# 1-MCU.net
KiCad netlist of a schematic drawn in Altium Designer
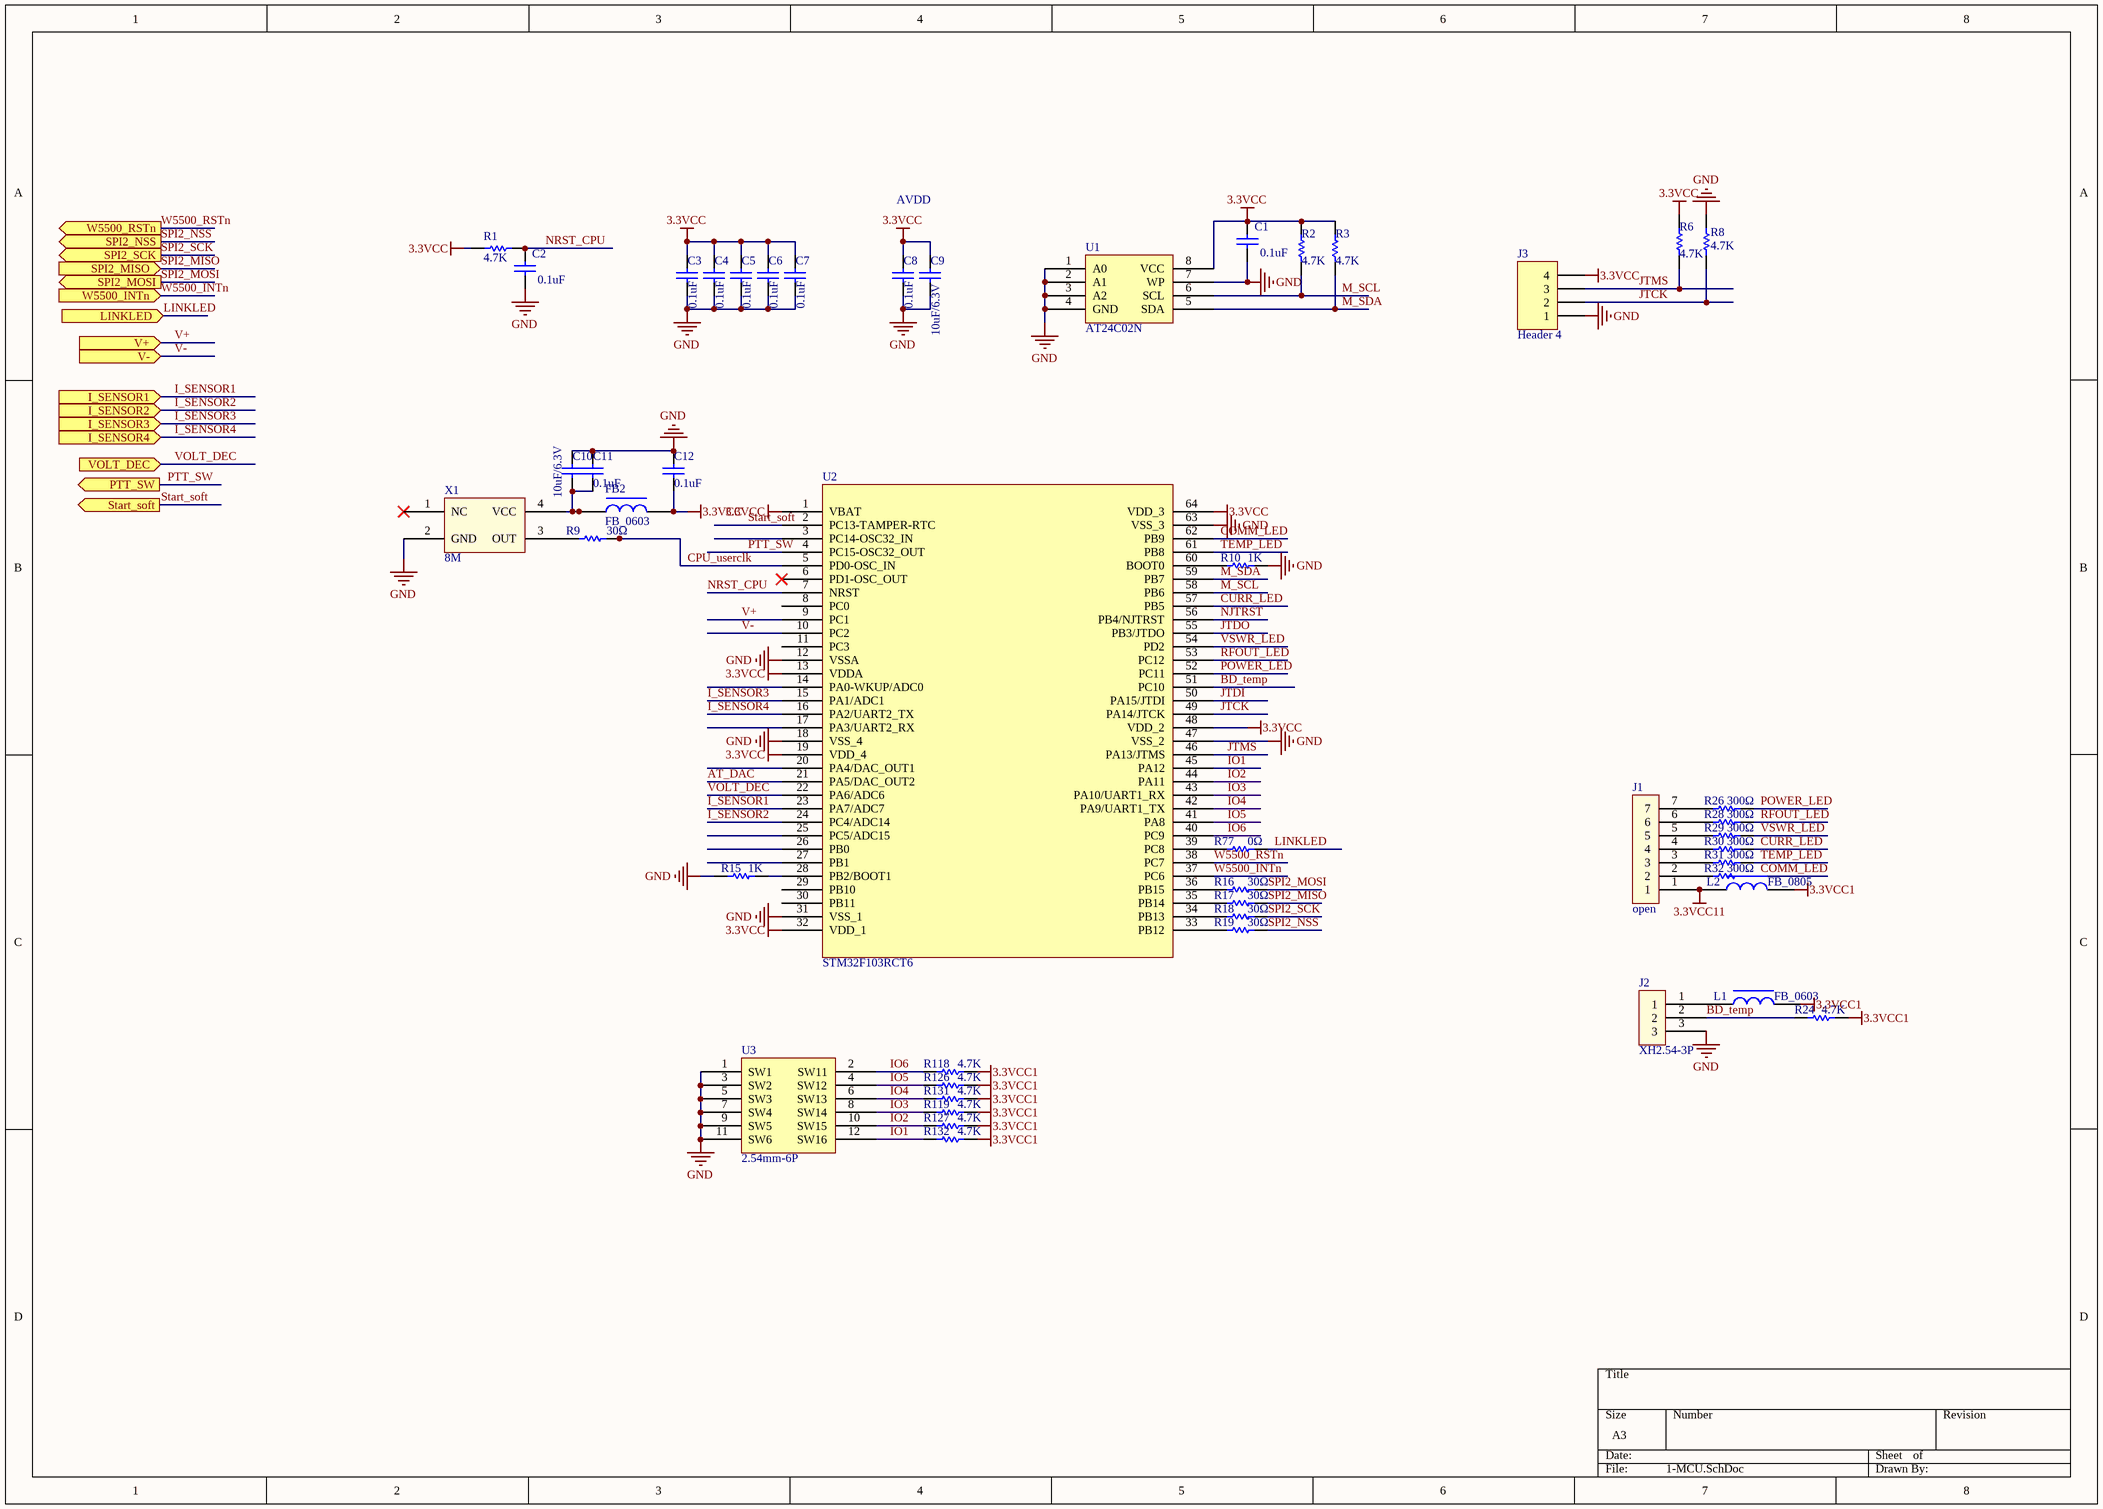
[diagram p0: 1-MCU.SchDoc]

(export (version "E")
  (design (tool "Eeschema 10.0.6"))
  (components
    (comp (ref "C1")
      (value "0.1uF")
      (footprint "C0603")
      (description "贴片电容_GRM188R71H104KA01D_0.1uF±10%,50V,0603")
      (libsource (lib "20贴片电容0603") (part "0.1uF贴片电容"))
    )
    (comp (ref "C2")
      (value "0.1uF")
      (footprint "C0603")
      (description "贴片电容_GRM188R71H104KA01D_0.1uF±10%,50V,0603")
      (libsource (lib "20贴片电容0603") (part "0.1uF贴片电容"))
    )
    (comp (ref "C3")
      (value "0.1uF")
      (footprint "C0603")
      (description "贴片电容_GRM188R71H104KA01D_0.1uF±10%,50V,0603")
      (libsource (lib "20贴片电容0603") (part "0.1uF贴片电容"))
    )
    (comp (ref "C4")
      (value "0.1uF")
      (footprint "C0603")
      (description "贴片电容_GRM188R71H104KA01D_0.1uF±10%,50V,0603")
      (libsource (lib "20贴片电容0603") (part "0.1uF贴片电容"))
    )
    (comp (ref "C5")
      (value "0.1uF")
      (footprint "C0603")
      (description "贴片电容_GRM188R71H104KA01D_0.1uF±10%,50V,0603")
      (libsource (lib "20贴片电容0603") (part "0.1uF贴片电容"))
    )
    (comp (ref "C6")
      (value "0.1uF")
      (footprint "C0603")
      (description "贴片电容_GRM188R71H104KA01D_0.1uF±10%,50V,0603")
      (libsource (lib "20贴片电容0603") (part "0.1uF贴片电容"))
    )
    (comp (ref "C7")
      (value "0.1uF")
      (footprint "C0603")
      (description "贴片电容_GRM188R71H104KA01D_0.1uF±10%,50V,0603")
      (libsource (lib "20贴片电容0603") (part "0.1uF贴片电容"))
    )
    (comp (ref "C8")
      (value "0.1uF")
      (footprint "C0603")
      (description "贴片电容_GRM188R71H104KA01D_0.1uF±10%,50V,0603")
      (libsource (lib "20贴片电容0603") (part "0.1uF贴片电容"))
    )
    (comp (ref "C9")
      (value "10uF/6.3V")
      (footprint "C0603")
      (description "贴片电容_GRM188R60J106ME47D_10uF±20%,6.3V,0603")
      (libsource (lib "20贴片电容0603") (part "10uF贴片电容"))
    )
    (comp (ref "C10")
      (value "10uF/6.3V")
      (footprint "C0603")
      (description "贴片电容_GRM188R60J106ME47D_10uF±20%,6.3V,0603")
      (libsource (lib "20贴片电容0603") (part "10uF贴片电容"))
    )
    (comp (ref "C11")
      (value "0.1uF")
      (footprint "C0603")
      (description "贴片电容_GRM188R71H104KA01D_0.1uF±10%,50V,0603")
      (libsource (lib "20贴片电容0603") (part "0.1uF贴片电容"))
    )
    (comp (ref "C12")
      (value "0.1uF")
      (footprint "C0603")
      (description "贴片电容_GRM188R71H104KA01D_0.1uF±10%,50V,0603")
      (libsource (lib "20贴片电容0603") (part "0.1uF贴片电容"))
    )
    (comp (ref "FB2")
      (value "FB_0603")
      (footprint "L0603")
      (description "贴片磁珠_100R,0603")
      (libsource (lib "32贴片磁珠0603") (part "0603贴片磁珠"))
    )
    (comp (ref "J1")
      (value "open")
      (footprint "KF2510-7P -2R54-17R8x6R0-wanzhen")
      (description "连接器_KF2510-7P_直插,间距2.54mm")
      (libsource (lib "91连接器") (part "KF2510-7P连接器"))
    )
    (comp (ref "J2")
      (value "XH2.54-3P")
      (footprint "pcblib:XH2.54mm-10R0x7R0--zhizhen")
      (description "连接器_XH2.54-3P_弯针,间距2.54mm")
      (libsource (lib "91连接器") (part "XH2.54-3P"))
    )
    (comp (ref "J3")
      (value "Header 4")
      (footprint "HDR1X4")
      (description "Header, 4-Pin")
      (fields (field (name "PUBLISHER") "Altium Limited"))
      (libsource (lib "Miscellaneous Connectors") (part "Header 4"))
    )
    (comp (ref "L1")
      (value "FB_0603")
      (footprint "L0603")
      (description "贴片磁珠_600R,0805")
      (libsource (lib "33贴片磁珠0805") (part "0805贴片磁珠"))
    )
    (comp (ref "L2")
      (value "FB_0805")
      (footprint "L0805")
      (description "贴片磁珠_600R,0805")
      (libsource (lib "33贴片磁珠0805") (part "0805贴片磁珠"))
    )
    (comp (ref "R1")
      (value "4.7K")
      (footprint "R0603")
      (description "贴片电阻_4.7K±5%,0603")
      (libsource (lib "10贴片电阻0603") (part "4.7K贴片电阻"))
    )
    (comp (ref "R2")
      (value "4.7K")
      (footprint "R0603")
      (description "贴片电阻_4.7K±5%,0603")
      (libsource (lib "10贴片电阻0603") (part "4.7K贴片电阻"))
    )
    (comp (ref "R3")
      (value "4.7K")
      (footprint "R0603")
      (description "贴片电阻_4.7K±5%,0603")
      (libsource (lib "10贴片电阻0603") (part "4.7K贴片电阻"))
    )
    (comp (ref "R6")
      (value "4.7K")
      (footprint "R0603")
      (description "贴片电阻_4.7K±5%,0603")
      (libsource (lib "10贴片电阻0603") (part "4.7K贴片电阻"))
    )
    (comp (ref "R8")
      (value "4.7K")
      (footprint "R0603")
      (description "贴片电阻_1K±5%,0603")
      (libsource (lib "10贴片电阻0603") (part "1K贴片电阻"))
    )
    (comp (ref "R9")
      (value "30Ω")
      (footprint "R0603")
      (description "贴片电阻_30Ω±5%,0603")
      (libsource (lib "10贴片电阻0603") (part "30Ω贴片电阻"))
    )
    (comp (ref "R10")
      (value "1K")
      (footprint "R0603")
      (description "贴片电阻_1K±5%,0603")
      (libsource (lib "10贴片电阻0603") (part "1K贴片电阻"))
    )
    (comp (ref "R15")
      (value "1K")
      (footprint "R0603")
      (description "贴片电阻_1K±5%,0603")
      (libsource (lib "10贴片电阻0603") (part "1K贴片电阻"))
    )
    (comp (ref "R16")
      (value "30Ω")
      (footprint "R0603")
      (description "贴片电阻_30Ω±5%,0603")
      (libsource (lib "10贴片电阻0603") (part "30Ω贴片电阻"))
    )
    (comp (ref "R17")
      (value "30Ω")
      (footprint "R0603")
      (description "贴片电阻_30Ω±5%,0603")
      (libsource (lib "10贴片电阻0603") (part "30Ω贴片电阻"))
    )
    (comp (ref "R18")
      (value "30Ω")
      (footprint "R0603")
      (description "贴片电阻_30Ω±5%,0603")
      (libsource (lib "10贴片电阻0603") (part "30Ω贴片电阻"))
    )
    (comp (ref "R19")
      (value "30Ω")
      (footprint "R0603")
      (description "贴片电阻_30Ω±5%,0603")
      (libsource (lib "10贴片电阻0603") (part "30Ω贴片电阻"))
    )
    (comp (ref "R24")
      (value "4.7K")
      (footprint "R0603")
      (description "贴片电阻_4.7K±5%,0603")
      (libsource (lib "10贴片电阻0603") (part "4.7K贴片电阻"))
    )
    (comp (ref "R26")
      (value "300Ω")
      (footprint "R0603")
      (description "贴片电阻_300Ω±5%,0603")
      (libsource (lib "10贴片电阻0603") (part "300Ω贴片电阻"))
    )
    (comp (ref "R28")
      (value "300Ω")
      (footprint "R0603")
      (description "贴片电阻_300Ω±5%,0603")
      (libsource (lib "10贴片电阻0603") (part "300Ω贴片电阻"))
    )
    (comp (ref "R29")
      (value "300Ω")
      (footprint "R0603")
      (description "贴片电阻_300Ω±5%,0603")
      (libsource (lib "10贴片电阻0603") (part "300Ω贴片电阻"))
    )
    (comp (ref "R30")
      (value "300Ω")
      (footprint "R0603")
      (description "贴片电阻_300Ω±5%,0603")
      (libsource (lib "10贴片电阻0603") (part "300Ω贴片电阻"))
    )
    (comp (ref "R31")
      (value "300Ω")
      (footprint "R0603")
      (description "贴片电阻_300Ω±5%,0603")
      (libsource (lib "10贴片电阻0603") (part "300Ω贴片电阻"))
    )
    (comp (ref "R32")
      (value "300Ω")
      (footprint "R0603")
      (description "贴片电阻_300Ω±5%,0603")
      (libsource (lib "10贴片电阻0603") (part "300Ω贴片电阻"))
    )
    (comp (ref "R77")
      (value "0Ω")
      (footprint "R0603")
      (description "贴片电阻_0Ω±5%,0603")
      (libsource (lib "10贴片电阻0603") (part "0Ω贴片电阻"))
    )
    (comp (ref "R118")
      (value "4.7K")
      (footprint "R0603")
      (description "贴片电阻_4.7K±5%,0603")
      (libsource (lib "10贴片电阻0603") (part "1.5K贴片电阻"))
    )
    (comp (ref "R119")
      (value "4.7K")
      (footprint "R0603")
      (description "贴片电阻_4.7K±5%,0603")
      (libsource (lib "10贴片电阻0603") (part "1.5K贴片电阻"))
    )
    (comp (ref "R126")
      (value "4.7K")
      (footprint "R0603")
      (description "贴片电阻_4.7K±5%,0603")
      (libsource (lib "10贴片电阻0603") (part "1.5K贴片电阻"))
    )
    (comp (ref "R127")
      (value "4.7K")
      (footprint "R0603")
      (description "贴片电阻_4.7K±5%,0603")
      (libsource (lib "10贴片电阻0603") (part "1.5K贴片电阻"))
    )
    (comp (ref "R131")
      (value "4.7K")
      (footprint "R0603")
      (description "贴片电阻_4.7K±5%,0603")
      (libsource (lib "10贴片电阻0603") (part "1.5K贴片电阻"))
    )
    (comp (ref "R132")
      (value "4.7K")
      (footprint "R0603")
      (description "贴片电阻_4.7K±5%,0603")
      (libsource (lib "10贴片电阻0603") (part "1.5K贴片电阻"))
    )
    (comp (ref "U1")
      (value "AT24C02N")
      (footprint "SOIC8_1R27_3R9x4R9")
      (description "EEPROM_AT24C02N_SOIC8")
      (libsource (lib "82存储器") (part "AT24C02N"))
    )
    (comp (ref "U2")
      (value "STM32F103RCT6")
      (footprint "LQFP64-0R50-10x10")
      (description "MCU_STM32F103RCT6_32bit,LQFP64")
      (libsource (lib "71单片机") (part "STM32F103RCT6"))
    )
    (comp (ref "U3")
      (value "2.54mm-6P")
      (footprint "pcblib:con12TM-2R54-2X6-boma")
      (description "拨码开关_2.54mm-6P_侧拨")
      (libsource (lib "81开关&门电路芯片") (part "拨码开关"))
    )
    (comp (ref "X1")
      (value "8M")
      (footprint "CRY4SM-5R0x7R0")
      (description "贴片有源晶振_8M,20ppm,封装5x7")
      (libsource (lib "60振荡器") (part "16M贴片有源晶振"))
    )
  )
  (nets
    (net (code "1") (name "/AT_DAC") (class "Default")
      (node (ref "U2") (pin "21") (pinfunction "PA5/DAC_OUT2_21") (pintype "passive"))
    )
    (net (code "2") (name "/BD_temp") (class "Default")
      (node (ref "J2") (pin "2") (pinfunction "2_2") (pintype "passive"))
      (node (ref "R24") (pin "2") (pinfunction "2_2") (pintype "passive"))
      (node (ref "U2") (pin "51") (pinfunction "PC10_51") (pintype "passive"))
    )
    (net (code "3") (name "/COMM_LED") (class "Default")
      (node (ref "R32") (pin "2") (pinfunction "2_2") (pintype "passive"))
      (node (ref "U2") (pin "62") (pinfunction "PB9_62") (pintype "passive"))
    )
    (net (code "4") (name "/CPU_userclk") (class "Default")
      (node (ref "R9") (pin "2") (pinfunction "2_2") (pintype "passive"))
      (node (ref "U2") (pin "5") (pinfunction "PD0-OSC_IN_5") (pintype "passive"))
    )
    (net (code "5") (name "/CURR_LED") (class "Default")
      (node (ref "R30") (pin "2") (pinfunction "2_2") (pintype "passive"))
      (node (ref "U2") (pin "57") (pinfunction "PB5_57") (pintype "passive"))
    )
    (net (code "6") (name "/IO1") (class "Default")
      (node (ref "R132") (pin "1") (pinfunction "1_1") (pintype "passive"))
      (node (ref "U2") (pin "45") (pinfunction "PA12_45") (pintype "passive"))
      (node (ref "U3") (pin "12") (pinfunction "SW16_12") (pintype "passive"))
    )
    (net (code "7") (name "/IO2") (class "Default")
      (node (ref "R127") (pin "1") (pinfunction "1_1") (pintype "passive"))
      (node (ref "U2") (pin "44") (pinfunction "PA11_44") (pintype "passive"))
      (node (ref "U3") (pin "10") (pinfunction "SW15_10") (pintype "passive"))
    )
    (net (code "8") (name "/IO3") (class "Default")
      (node (ref "R119") (pin "1") (pinfunction "1_1") (pintype "passive"))
      (node (ref "U2") (pin "43") (pinfunction "PA10/UART1_RX_43") (pintype "passive"))
      (node (ref "U3") (pin "8") (pinfunction "SW14_8") (pintype "passive"))
    )
    (net (code "9") (name "/IO4") (class "Default")
      (node (ref "R131") (pin "1") (pinfunction "1_1") (pintype "passive"))
      (node (ref "U2") (pin "42") (pinfunction "PA9/UART1_TX_42") (pintype "passive"))
      (node (ref "U3") (pin "6") (pinfunction "SW13_6") (pintype "passive"))
    )
    (net (code "10") (name "/IO5") (class "Default")
      (node (ref "R126") (pin "1") (pinfunction "1_1") (pintype "passive"))
      (node (ref "U2") (pin "41") (pinfunction "PA8_41") (pintype "passive"))
      (node (ref "U3") (pin "4") (pinfunction "SW12_4") (pintype "passive"))
    )
    (net (code "11") (name "/IO6") (class "Default")
      (node (ref "R118") (pin "1") (pinfunction "1_1") (pintype "passive"))
      (node (ref "U2") (pin "40") (pinfunction "PC9_40") (pintype "passive"))
      (node (ref "U3") (pin "2") (pinfunction "SW11_2") (pintype "passive"))
    )
    (net (code "12") (name "/I_SENSOR1") (class "Default")
      (node (ref "U2") (pin "23") (pinfunction "PA7/ADC7_23") (pintype "passive"))
    )
    (net (code "13") (name "/I_SENSOR2") (class "Default")
      (node (ref "U2") (pin "24") (pinfunction "PC4/ADC14_24") (pintype "passive"))
    )
    (net (code "14") (name "/I_SENSOR3") (class "Default")
      (node (ref "U2") (pin "15") (pinfunction "PA1/ADC1_15") (pintype "passive"))
    )
    (net (code "15") (name "/I_SENSOR4") (class "Default")
      (node (ref "U2") (pin "16") (pinfunction "PA2/UART2_TX_16") (pintype "passive"))
    )
    (net (code "16") (name "/JTCK") (class "Default")
      (node (ref "J3") (pin "2") (pinfunction "2_2") (pintype "passive"))
      (node (ref "R8") (pin "2") (pinfunction "2_2") (pintype "passive"))
      (node (ref "U2") (pin "49") (pinfunction "PA14/JTCK_49") (pintype "passive"))
    )
    (net (code "17") (name "/JTDI") (class "Default")
      (node (ref "U2") (pin "50") (pinfunction "PA15/JTDI_50") (pintype "passive"))
    )
    (net (code "18") (name "/JTDO") (class "Default")
      (node (ref "U2") (pin "55") (pinfunction "PB3/JTDO_55") (pintype "passive"))
    )
    (net (code "19") (name "/JTMS") (class "Default")
      (node (ref "J3") (pin "3") (pinfunction "3_3") (pintype "passive"))
      (node (ref "R6") (pin "1") (pinfunction "1_1") (pintype "passive"))
      (node (ref "U2") (pin "46") (pinfunction "PA13/JTMS_46") (pintype "passive"))
    )
    (net (code "20") (name "/LINKLED") (class "Default")
      (node (ref "R77") (pin "2") (pinfunction "2_2") (pintype "passive"))
    )
    (net (code "21") (name "/M_SCL") (class "Default")
      (node (ref "R2") (pin "1") (pinfunction "1_1") (pintype "passive"))
      (node (ref "U1") (pin "6") (pinfunction "SCL_6") (pintype "passive"))
      (node (ref "U2") (pin "58") (pinfunction "PB6_58") (pintype "passive"))
    )
    (net (code "22") (name "/M_SDA") (class "Default")
      (node (ref "R3") (pin "1") (pinfunction "1_1") (pintype "passive"))
      (node (ref "U1") (pin "5") (pinfunction "SDA_5") (pintype "passive"))
      (node (ref "U2") (pin "59") (pinfunction "PB7_59") (pintype "passive"))
    )
    (net (code "23") (name "/NJTRST") (class "Default")
      (node (ref "U2") (pin "56") (pinfunction "PB4/NJTRST_56") (pintype "passive"))
    )
    (net (code "24") (name "/NRST_CPU") (class "Default")
      (node (ref "C2") (pin "2") (pinfunction "2_2") (pintype "passive"))
      (node (ref "R1") (pin "1") (pinfunction "1_1") (pintype "passive"))
      (node (ref "U2") (pin "7") (pinfunction "NRST_7") (pintype "passive"))
    )
    (net (code "25") (name "/POWER_LED") (class "Default")
      (node (ref "R26") (pin "2") (pinfunction "2_2") (pintype "passive"))
      (node (ref "U2") (pin "52") (pinfunction "PC11_52") (pintype "passive"))
    )
    (net (code "26") (name "/PTT_SW") (class "Default")
      (node (ref "U2") (pin "4") (pinfunction "PC15-OSC32_OUT_4") (pintype "passive"))
    )
    (net (code "27") (name "/RFOUT_LED") (class "Default")
      (node (ref "R28") (pin "2") (pinfunction "2_2") (pintype "passive"))
      (node (ref "U2") (pin "53") (pinfunction "PC12_53") (pintype "passive"))
    )
    (net (code "28") (name "/SPI2_MISO") (class "Default")
      (node (ref "R17") (pin "2") (pinfunction "2_2") (pintype "passive"))
    )
    (net (code "29") (name "/SPI2_MOSI") (class "Default")
      (node (ref "R16") (pin "2") (pinfunction "2_2") (pintype "passive"))
    )
    (net (code "30") (name "/SPI2_NSS") (class "Default")
      (node (ref "R19") (pin "2") (pinfunction "2_2") (pintype "passive"))
    )
    (net (code "31") (name "/SPI2_SCK") (class "Default")
      (node (ref "R18") (pin "2") (pinfunction "2_2") (pintype "passive"))
    )
    (net (code "32") (name "/Start_soft") (class "Default")
      (node (ref "U2") (pin "2") (pinfunction "PC13-TAMPER-RTC_2") (pintype "passive"))
    )
    (net (code "33") (name "/TEMP_LED") (class "Default")
      (node (ref "R31") (pin "2") (pinfunction "2_2") (pintype "passive"))
      (node (ref "U2") (pin "61") (pinfunction "PB8_61") (pintype "passive"))
    )
    (net (code "34") (name "/V+") (class "Default")
      (node (ref "U2") (pin "9") (pinfunction "PC1_9") (pintype "passive"))
    )
    (net (code "35") (name "/V-") (class "Default")
      (node (ref "U2") (pin "10") (pinfunction "PC2_10") (pintype "passive"))
    )
    (net (code "36") (name "/VOLT_DEC") (class "Default")
      (node (ref "U2") (pin "22") (pinfunction "PA6/ADC6_22") (pintype "passive"))
    )
    (net (code "37") (name "/VSWR_LED") (class "Default")
      (node (ref "R29") (pin "2") (pinfunction "2_2") (pintype "passive"))
      (node (ref "U2") (pin "54") (pinfunction "PD2_54") (pintype "passive"))
    )
    (net (code "38") (name "/W5500_INTn") (class "Default")
      (node (ref "U2") (pin "37") (pinfunction "PC6_37") (pintype "passive"))
    )
    (net (code "39") (name "/W5500_RSTn") (class "Default")
      (node (ref "U2") (pin "38") (pinfunction "PC7_38") (pintype "passive"))
    )
    (net (code "40") (name "3.3VCC") (class "Default")
      (node (ref "C1") (pin "2") (pinfunction "2_2") (pintype "passive"))
      (node (ref "C12") (pin "1") (pinfunction "1_1") (pintype "passive"))
      (node (ref "C3") (pin "2") (pinfunction "2_2") (pintype "passive"))
      (node (ref "C4") (pin "2") (pinfunction "2_2") (pintype "passive"))
      (node (ref "C5") (pin "2") (pinfunction "2_2") (pintype "passive"))
      (node (ref "C6") (pin "2") (pinfunction "2_2") (pintype "passive"))
      (node (ref "C7") (pin "2") (pinfunction "2_2") (pintype "passive"))
      (node (ref "C8") (pin "2") (pinfunction "2_2") (pintype "passive"))
      (node (ref "C9") (pin "2") (pinfunction "2_2") (pintype "passive"))
      (node (ref "FB2") (pin "2") (pinfunction "2_2") (pintype "passive"))
      (node (ref "J3") (pin "4") (pinfunction "4_4") (pintype "passive"))
      (node (ref "R1") (pin "2") (pinfunction "2_2") (pintype "passive"))
      (node (ref "R2") (pin "2") (pinfunction "2_2") (pintype "passive"))
      (node (ref "R3") (pin "2") (pinfunction "2_2") (pintype "passive"))
      (node (ref "R6") (pin "2") (pinfunction "2_2") (pintype "passive"))
      (node (ref "U1") (pin "8") (pinfunction "VCC_8") (pintype "passive"))
      (node (ref "U2") (pin "1") (pinfunction "VBAT_1") (pintype "passive"))
      (node (ref "U2") (pin "13") (pinfunction "VDDA_13") (pintype "passive"))
      (node (ref "U2") (pin "19") (pinfunction "VDD_4_19") (pintype "passive"))
      (node (ref "U2") (pin "32") (pinfunction "VDD_1_32") (pintype "passive"))
      (node (ref "U2") (pin "48") (pinfunction "VDD_2_48") (pintype "passive"))
      (node (ref "U2") (pin "64") (pinfunction "VDD_3_64") (pintype "passive"))
    )
    (net (code "41") (name "3.3VCC1") (class "Default")
      (node (ref "L1") (pin "2") (pinfunction "2_2") (pintype "passive"))
      (node (ref "L2") (pin "2") (pinfunction "2_2") (pintype "passive"))
      (node (ref "R118") (pin "2") (pinfunction "2_2") (pintype "passive"))
      (node (ref "R119") (pin "2") (pinfunction "2_2") (pintype "passive"))
      (node (ref "R126") (pin "2") (pinfunction "2_2") (pintype "passive"))
      (node (ref "R127") (pin "2") (pinfunction "2_2") (pintype "passive"))
      (node (ref "R131") (pin "2") (pinfunction "2_2") (pintype "passive"))
      (node (ref "R132") (pin "2") (pinfunction "2_2") (pintype "passive"))
      (node (ref "R24") (pin "1") (pinfunction "1_1") (pintype "passive"))
    )
    (net (code "42") (name "3.3VCC11") (class "Default")
      (node (ref "J1") (pin "1") (pinfunction "1_1") (pintype "passive"))
      (node (ref "L2") (pin "1") (pinfunction "1_1") (pintype "passive"))
    )
    (net (code "43") (name "GND") (class "Default")
      (node (ref "C1") (pin "1") (pinfunction "1_1") (pintype "passive"))
      (node (ref "C10") (pin "1") (pinfunction "1_1") (pintype "passive"))
      (node (ref "C11") (pin "2") (pinfunction "2_2") (pintype "passive"))
      (node (ref "C12") (pin "2") (pinfunction "2_2") (pintype "passive"))
      (node (ref "C2") (pin "1") (pinfunction "1_1") (pintype "passive"))
      (node (ref "C3") (pin "1") (pinfunction "1_1") (pintype "passive"))
      (node (ref "C4") (pin "1") (pinfunction "1_1") (pintype "passive"))
      (node (ref "C5") (pin "1") (pinfunction "1_1") (pintype "passive"))
      (node (ref "C6") (pin "1") (pinfunction "1_1") (pintype "passive"))
      (node (ref "C7") (pin "1") (pinfunction "1_1") (pintype "passive"))
      (node (ref "C8") (pin "1") (pinfunction "1_1") (pintype "passive"))
      (node (ref "C9") (pin "1") (pinfunction "1_1") (pintype "passive"))
      (node (ref "J2") (pin "3") (pinfunction "3_3") (pintype "passive"))
      (node (ref "J3") (pin "1") (pinfunction "1_1") (pintype "passive"))
      (node (ref "R10") (pin "1") (pinfunction "1_1") (pintype "passive"))
      (node (ref "R15") (pin "1") (pinfunction "1_1") (pintype "passive"))
      (node (ref "R8") (pin "1") (pinfunction "1_1") (pintype "passive"))
      (node (ref "U1") (pin "1") (pinfunction "A0_1") (pintype "passive"))
      (node (ref "U1") (pin "2") (pinfunction "A1_2") (pintype "passive"))
      (node (ref "U1") (pin "3") (pinfunction "A2_3") (pintype "passive"))
      (node (ref "U1") (pin "4") (pinfunction "GND_4") (pintype "passive"))
      (node (ref "U1") (pin "7") (pinfunction "WP_7") (pintype "passive"))
      (node (ref "U2") (pin "12") (pinfunction "VSSA_12") (pintype "passive"))
      (node (ref "U2") (pin "18") (pinfunction "VSS_4_18") (pintype "passive"))
      (node (ref "U2") (pin "31") (pinfunction "VSS_1_31") (pintype "passive"))
      (node (ref "U2") (pin "47") (pinfunction "VSS_2_47") (pintype "passive"))
      (node (ref "U2") (pin "63") (pinfunction "VSS_3_63") (pintype "passive"))
      (node (ref "U3") (pin "1") (pinfunction "SW1_1") (pintype "passive"))
      (node (ref "U3") (pin "11") (pinfunction "SW6_11") (pintype "passive"))
      (node (ref "U3") (pin "3") (pinfunction "SW2_3") (pintype "passive"))
      (node (ref "U3") (pin "5") (pinfunction "SW3_5") (pintype "passive"))
      (node (ref "U3") (pin "7") (pinfunction "SW4_7") (pintype "passive"))
      (node (ref "U3") (pin "9") (pinfunction "SW5_9") (pintype "passive"))
      (node (ref "X1") (pin "2") (pinfunction "GND_2") (pintype "passive"))
    )
    (net (code "44") (name "Net-(J1-Pad2)") (class "Default")
      (node (ref "J1") (pin "2") (pinfunction "2_2") (pintype "passive"))
      (node (ref "R32") (pin "1") (pinfunction "1_1") (pintype "passive"))
    )
    (net (code "45") (name "Net-(J1-Pad3)") (class "Default")
      (node (ref "J1") (pin "3") (pinfunction "3_3") (pintype "passive"))
      (node (ref "R31") (pin "1") (pinfunction "1_1") (pintype "passive"))
    )
    (net (code "46") (name "Net-(J1-Pad4)") (class "Default")
      (node (ref "J1") (pin "4") (pinfunction "4_4") (pintype "passive"))
      (node (ref "R30") (pin "1") (pinfunction "1_1") (pintype "passive"))
    )
    (net (code "47") (name "Net-(J1-Pad5)") (class "Default")
      (node (ref "J1") (pin "5") (pinfunction "5_5") (pintype "passive"))
      (node (ref "R29") (pin "1") (pinfunction "1_1") (pintype "passive"))
    )
    (net (code "48") (name "Net-(J1-Pad6)") (class "Default")
      (node (ref "J1") (pin "6") (pinfunction "6_6") (pintype "passive"))
      (node (ref "R28") (pin "1") (pinfunction "1_1") (pintype "passive"))
    )
    (net (code "49") (name "Net-(J1-Pad7)") (class "Default")
      (node (ref "J1") (pin "7") (pinfunction "7_7") (pintype "passive"))
      (node (ref "R26") (pin "1") (pinfunction "1_1") (pintype "passive"))
    )
    (net (code "50") (name "Net-(J2-Pad1)") (class "Default")
      (node (ref "J2") (pin "1") (pinfunction "1_1") (pintype "passive"))
      (node (ref "L1") (pin "1") (pinfunction "1_1") (pintype "passive"))
    )
    (net (code "51") (name "Net-(U2-BOOT0)") (class "Default")
      (node (ref "R10") (pin "2") (pinfunction "2_2") (pintype "passive"))
      (node (ref "U2") (pin "60") (pinfunction "BOOT0_60") (pintype "passive"))
    )
    (net (code "52") (name "Net-(U2-PB2{slash}BOOT1)") (class "Default")
      (node (ref "R15") (pin "2") (pinfunction "2_2") (pintype "passive"))
      (node (ref "U2") (pin "28") (pinfunction "PB2/BOOT1_28") (pintype "passive"))
    )
    (net (code "53") (name "Net-(U2-PB12)") (class "Default")
      (node (ref "R19") (pin "1") (pinfunction "1_1") (pintype "passive"))
      (node (ref "U2") (pin "33") (pinfunction "PB12_33") (pintype "passive"))
    )
    (net (code "54") (name "Net-(U2-PB13)") (class "Default")
      (node (ref "R18") (pin "1") (pinfunction "1_1") (pintype "passive"))
      (node (ref "U2") (pin "34") (pinfunction "PB13_34") (pintype "passive"))
    )
    (net (code "55") (name "Net-(U2-PB14)") (class "Default")
      (node (ref "R17") (pin "1") (pinfunction "1_1") (pintype "passive"))
      (node (ref "U2") (pin "35") (pinfunction "PB14_35") (pintype "passive"))
    )
    (net (code "56") (name "Net-(U2-PB15)") (class "Default")
      (node (ref "R16") (pin "1") (pinfunction "1_1") (pintype "passive"))
      (node (ref "U2") (pin "36") (pinfunction "PB15_36") (pintype "passive"))
    )
    (net (code "57") (name "Net-(U2-PC8)") (class "Default")
      (node (ref "R77") (pin "1") (pinfunction "1_1") (pintype "passive"))
      (node (ref "U2") (pin "39") (pinfunction "PC8_39") (pintype "passive"))
    )
    (net (code "58") (name "Net-(X1-OUT)") (class "Default")
      (node (ref "R9") (pin "1") (pinfunction "1_1") (pintype "passive"))
      (node (ref "X1") (pin "3") (pinfunction "OUT_3") (pintype "passive"))
    )
    (net (code "59") (name "Net-(X1-VCC)") (class "Default")
      (node (ref "C10") (pin "2") (pinfunction "2_2") (pintype "passive"))
      (node (ref "C11") (pin "1") (pinfunction "1_1") (pintype "passive"))
      (node (ref "FB2") (pin "1") (pinfunction "1_1") (pintype "passive"))
      (node (ref "X1") (pin "4") (pinfunction "VCC_4") (pintype "passive"))
    )
    (net (code "60") (name "unconnected-(U2-PA0-WKUP{slash}ADC0-Pad14)") (class "Default")
      (node (ref "U2") (pin "14") (pinfunction "PA0-WKUP/ADC0_14") (pintype "passive"))
    )
    (net (code "61") (name "unconnected-(U2-PA3{slash}UART2_RX-Pad17)") (class "Default")
      (node (ref "U2") (pin "17") (pinfunction "PA3/UART2_RX_17") (pintype "passive"))
    )
    (net (code "62") (name "unconnected-(U2-PA4{slash}DAC_OUT1-Pad20)") (class "Default")
      (node (ref "U2") (pin "20") (pinfunction "PA4/DAC_OUT1_20") (pintype "passive"))
    )
    (net (code "63") (name "unconnected-(U2-PB0-Pad26)") (class "Default")
      (node (ref "U2") (pin "26") (pinfunction "PB0_26") (pintype "passive"))
    )
    (net (code "64") (name "unconnected-(U2-PB1-Pad27)") (class "Default")
      (node (ref "U2") (pin "27") (pinfunction "PB1_27") (pintype "passive"))
    )
    (net (code "65") (name "unconnected-(U2-PB10-Pad29)") (class "Default")
      (node (ref "U2") (pin "29") (pinfunction "PB10_29") (pintype "passive"))
    )
    (net (code "66") (name "unconnected-(U2-PB11-Pad30)") (class "Default")
      (node (ref "U2") (pin "30") (pinfunction "PB11_30") (pintype "passive"))
    )
    (net (code "67") (name "unconnected-(U2-PC0-Pad8)") (class "Default")
      (node (ref "U2") (pin "8") (pinfunction "PC0_8") (pintype "passive"))
    )
    (net (code "68") (name "unconnected-(U2-PC3-Pad11)") (class "Default")
      (node (ref "U2") (pin "11") (pinfunction "PC3_11") (pintype "passive"))
    )
    (net (code "69") (name "unconnected-(U2-PC5{slash}ADC15-Pad25)") (class "Default")
      (node (ref "U2") (pin "25") (pinfunction "PC5/ADC15_25") (pintype "passive"))
    )
    (net (code "70") (name "unconnected-(U2-PC14-OSC32_IN-Pad3)") (class "Default")
      (node (ref "U2") (pin "3") (pinfunction "PC14-OSC32_IN_3") (pintype "passive"))
    )
    (net (code "71") (name "unconnected-(U2-PD1-OSC_OUT-Pad6)") (class "Default")
      (node (ref "U2") (pin "6") (pinfunction "PD1-OSC_OUT_6") (pintype "passive+no_connect"))
    )
    (net (code "72") (name "unconnected-(X1-NC-Pad1)") (class "Default")
      (node (ref "X1") (pin "1") (pinfunction "NC_1") (pintype "passive+no_connect"))
    )
  )
)
